# Stimulus_Feedback.net
KiCad netlist of a schematic drawn in Altium Designer
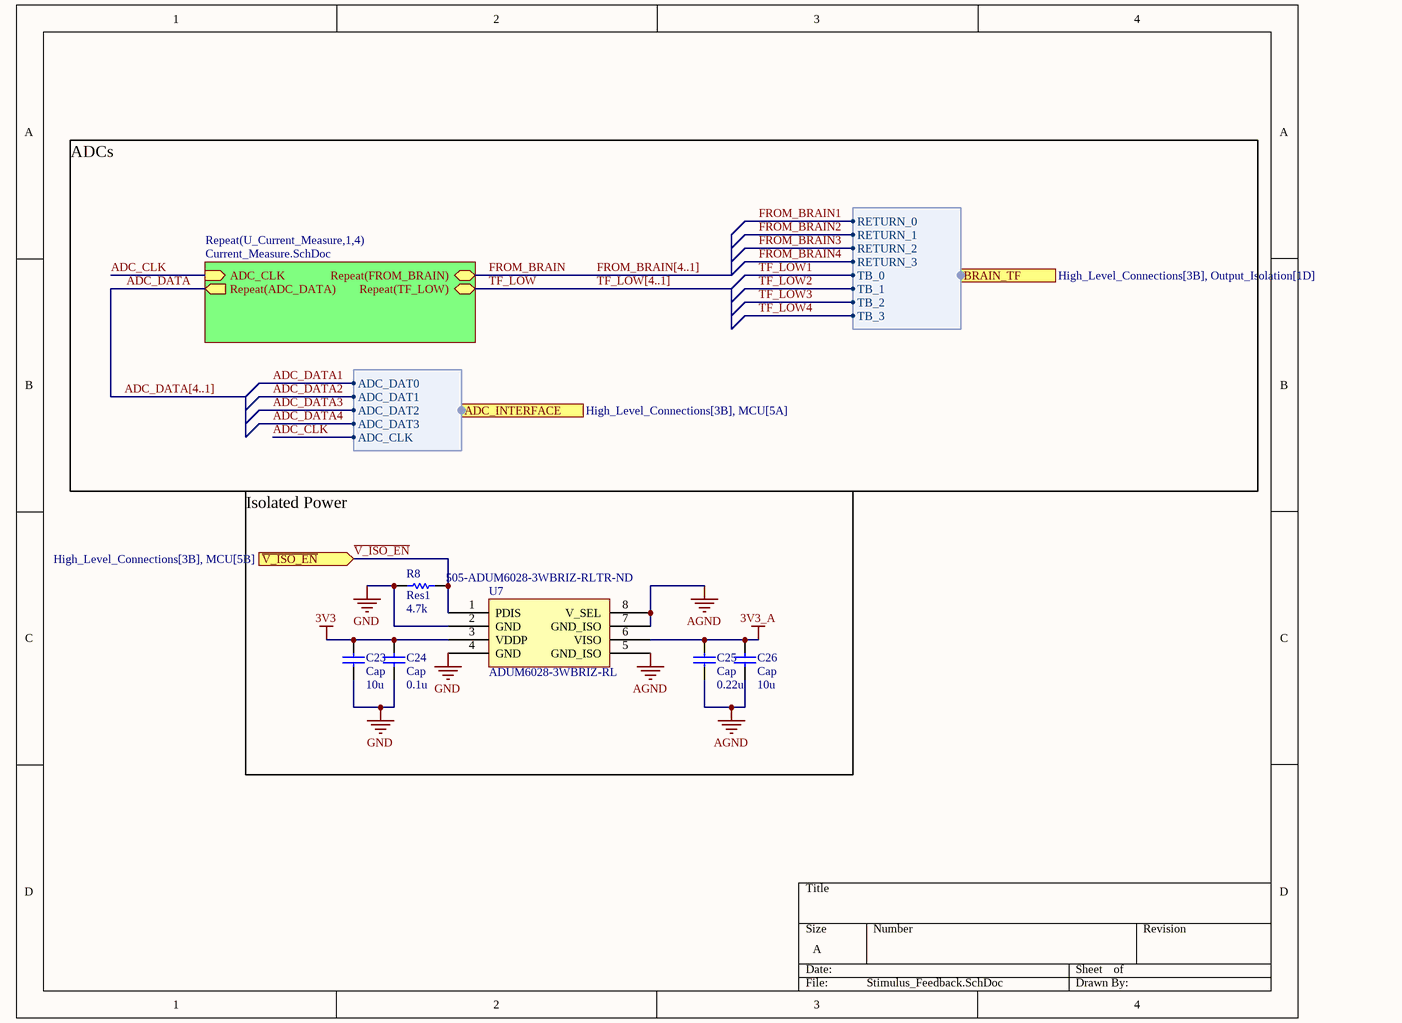
[diagram p0: Stimulus_Feedback.SchDoc]

(export (version "E")
  (design (tool "Eeschema 10.0.6"))
  (components
    (comp (ref "C23")
      (value "Cap")
      (footprint "CAPC1608X05N")
      (description "Capacitor")
      (fields (field (name "ALTIUM_VALUE") "10u") (field (name "PUBLISHER") "Altium Limited"))
      (libsource (lib "Miscellaneous Devices") (part "Cap"))
    )
    (comp (ref "C24")
      (value "Cap")
      (footprint "CAPC1608X05N")
      (description "Capacitor")
      (fields (field (name "ALTIUM_VALUE") "0.1u") (field (name "PUBLISHER") "Altium Limited"))
      (libsource (lib "Miscellaneous Devices") (part "Cap"))
    )
    (comp (ref "C25")
      (value "Cap")
      (footprint "CAPC1608X05N")
      (description "Capacitor")
      (fields (field (name "ALTIUM_VALUE") "0.22u") (field (name "PUBLISHER") "Altium Limited"))
      (libsource (lib "Miscellaneous Devices") (part "Cap"))
    )
    (comp (ref "C26")
      (value "Cap")
      (footprint "CAPC1608X05N")
      (description "Capacitor")
      (fields (field (name "ALTIUM_VALUE") "10u") (field (name "PUBLISHER") "Altium Limited"))
      (libsource (lib "Miscellaneous Devices") (part "Cap"))
    )
    (comp (ref "R8")
      (value "Res1")
      (footprint "0402_Res")
      (description "Resistor")
      (fields (field (name "ALTIUM_VALUE") "4.7k") (field (name "PUBLISHER") "Altium Limited"))
      (libsource (lib "Miscellaneous Devices") (part "Res1"))
    )
    (comp (ref "U7")
      (value "ADUM6028-3WBRIZ-RL")
      (footprint "ADUM6028-3WBRIZ-RL")
      (fields (field (name "SUPPLIER PART NUMBER 1") "505-ADUM6028-3WBRIZ-RLTR-ND"))
      (libsource (lib "Brain_Stim_Lib") (part "ADUM6028-3WBRIZ-RL"))
    )
  )
  (nets
    (net (code "23") (name "/~{V_ISO_EN}") (class "Default")
      (node (ref "R8") (pin "2") (pinfunction "2_2") (pintype "passive"))
      (node (ref "U7") (pin "1") (pinfunction "PDIS_1") (pintype "passive"))
    )
    (net (code "24") (name "3V3") (class "Default")
      (node (ref "C23") (pin "2") (pinfunction "2_2") (pintype "passive"))
      (node (ref "C24") (pin "2") (pinfunction "2_2") (pintype "passive"))
      (node (ref "U7") (pin "3") (pinfunction "VDDP_3") (pintype "passive"))
    )
    (net (code "25") (name "3V3_A") (class "Default")
      (node (ref "C25") (pin "2") (pinfunction "2_2") (pintype "passive"))
      (node (ref "C26") (pin "2") (pinfunction "2_2") (pintype "passive"))
      (node (ref "U7") (pin "6") (pinfunction "VISO_6") (pintype "passive"))
    )
    (net (code "26") (name "AGND") (class "Default")
      (node (ref "C25") (pin "1") (pinfunction "1_1") (pintype "passive"))
      (node (ref "C26") (pin "1") (pinfunction "1_1") (pintype "passive"))
      (node (ref "U7") (pin "5") (pinfunction "GND_ISO_5") (pintype "passive"))
      (node (ref "U7") (pin "7") (pinfunction "GND_ISO_7") (pintype "passive"))
      (node (ref "U7") (pin "8") (pinfunction "V_SEL_8") (pintype "passive"))
    )
    (net (code "27") (name "GND") (class "Default")
      (node (ref "C23") (pin "1") (pinfunction "1_1") (pintype "passive"))
      (node (ref "C24") (pin "1") (pinfunction "1_1") (pintype "passive"))
      (node (ref "R8") (pin "1") (pinfunction "1_1") (pintype "passive"))
      (node (ref "U7") (pin "2") (pinfunction "GND_2") (pintype "passive"))
      (node (ref "U7") (pin "4") (pinfunction "GND_4") (pintype "passive"))
    )
  )
)
